# readerstation.net
KiCad netlist of a schematic drawn in EAGLE
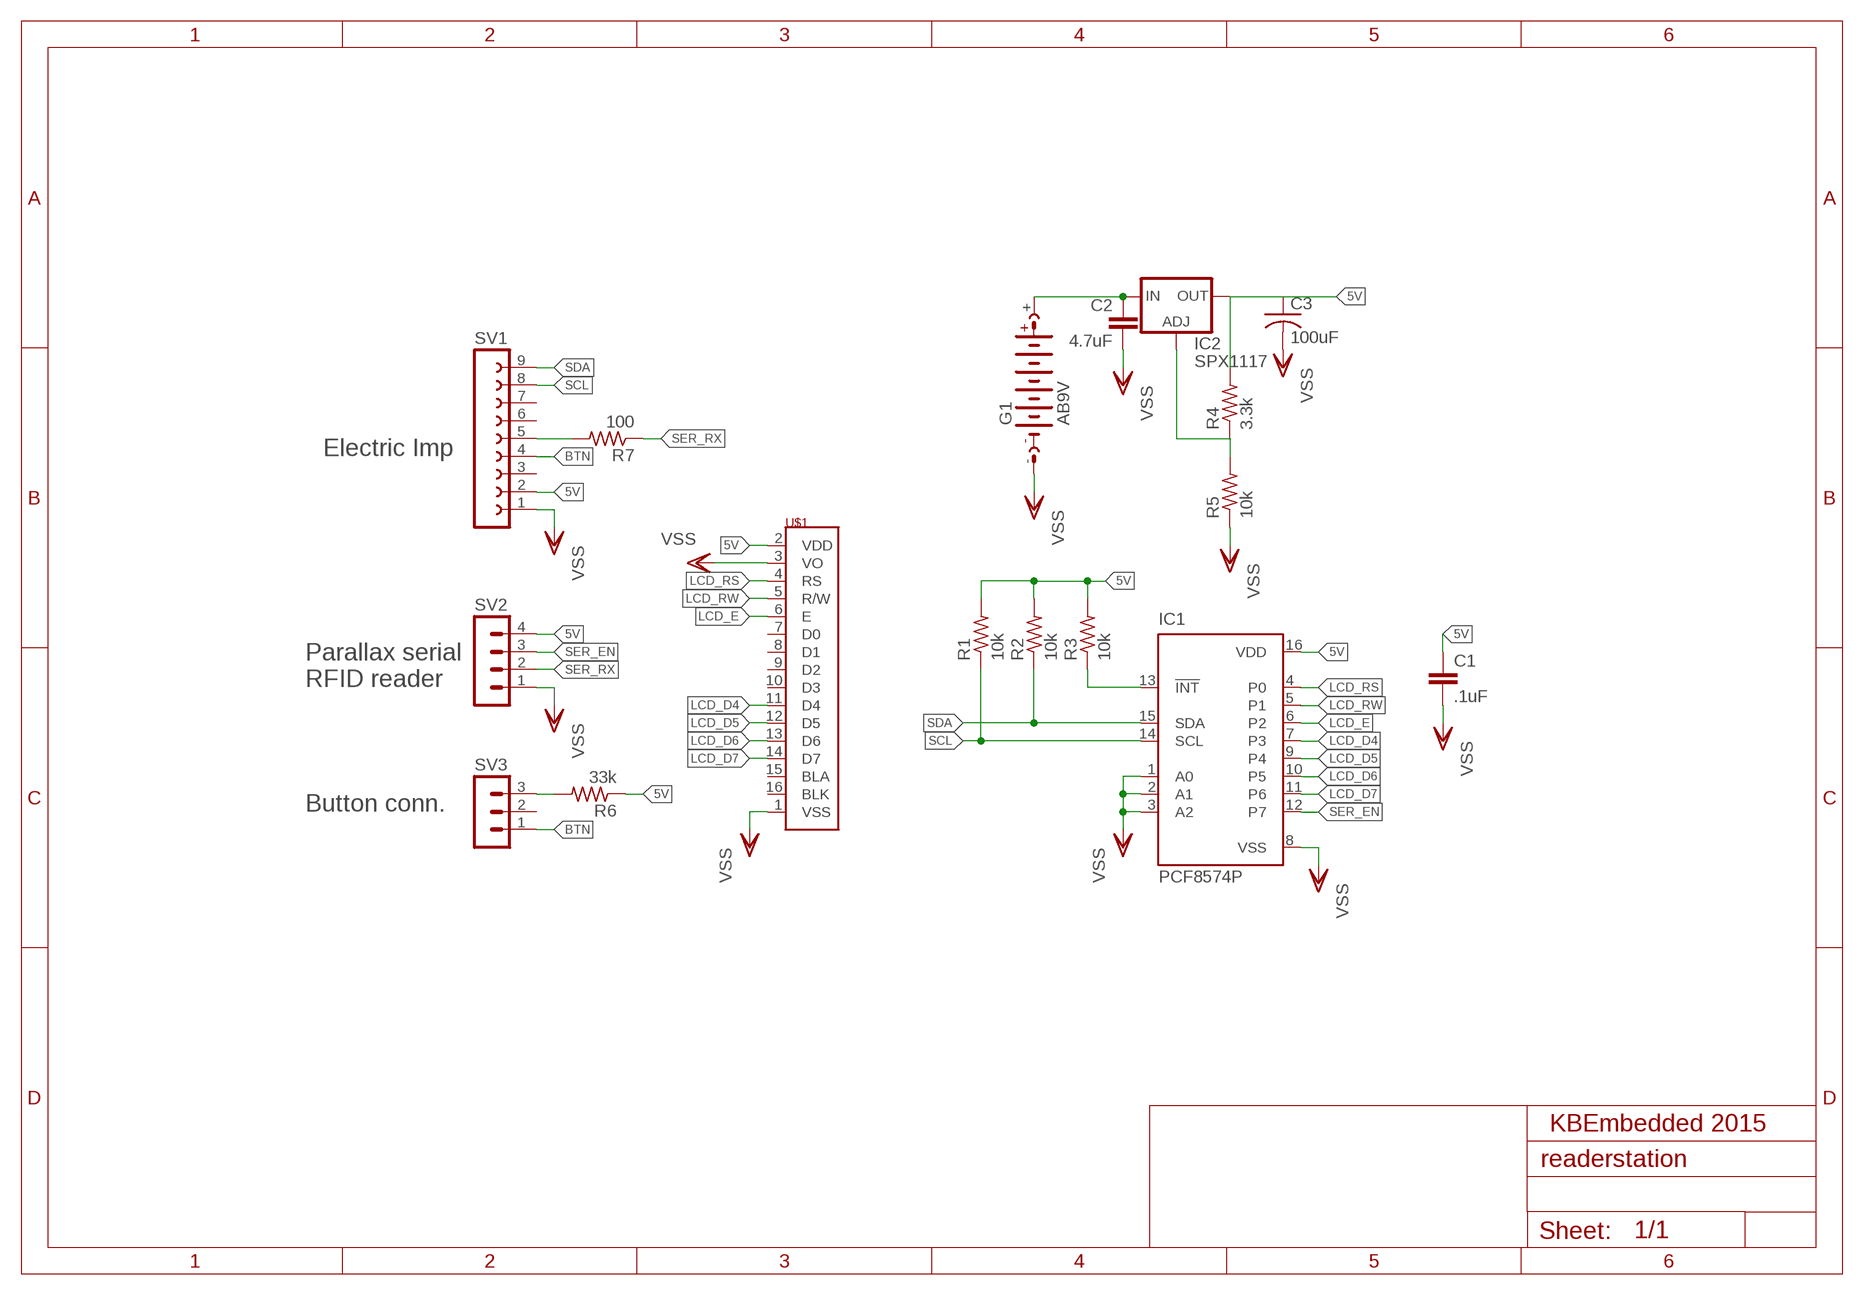
[diagram p0: schematic, sheet 1]

(export (version "E")
  (design (tool "Eeschema 10.0.6"))
  (components
    (comp (ref "C1")
      (value ".1uF")
      (footprint "eagle-import:C025-024X044")
      (libsource (lib "eagle-import") (part "C-EU025-024X044"))
    )
    (comp (ref "C2")
      (value "4.7uF")
      (footprint "eagle-import:C025-024X044")
      (libsource (lib "eagle-import") (part "C-EU025-024X044"))
    )
    (comp (ref "C3")
      (value "100uF")
      (footprint "eagle-import:C025-024X044")
      (libsource (lib "eagle-import") (part "C-US025-024X044"))
    )
    (comp (ref "G1")
      (value "AB9V")
      (footprint "eagle-import:AB9V")
      (libsource (lib "eagle-import") (part "AB9V"))
    )
    (comp (ref "IC1")
      (value "PCF8574P")
      (footprint "eagle-import:DIL16")
      (fields (field (name "MPN") "PCF8574PN"))
      (libsource (lib "eagle-import") (part "PCF8574P"))
    )
    (comp (ref "IC2")
      (value "SPX1117")
      (footprint "eagle-import:SOT223")
      (libsource (lib "eagle-import") (part "LD117A?S12TR"))
    )
    (comp (ref "R1")
      (value "10k")
      (footprint "eagle-import:0204_5")
      (libsource (lib "eagle-import") (part "R-US_0204/5"))
    )
    (comp (ref "R2")
      (value "10k")
      (footprint "eagle-import:0204_5")
      (libsource (lib "eagle-import") (part "R-US_0204/5"))
    )
    (comp (ref "R3")
      (value "10k")
      (footprint "eagle-import:0204_5")
      (libsource (lib "eagle-import") (part "R-US_0204/5"))
    )
    (comp (ref "R4")
      (value "3.3k")
      (footprint "eagle-import:0204_5")
      (libsource (lib "eagle-import") (part "R-US_0204/5"))
    )
    (comp (ref "R5")
      (value "10k")
      (footprint "eagle-import:0204_5")
      (libsource (lib "eagle-import") (part "R-US_0204/5"))
    )
    (comp (ref "R6")
      (value "33k")
      (footprint "eagle-import:0204_5")
      (libsource (lib "eagle-import") (part "R-US_0204/5"))
    )
    (comp (ref "R7")
      (value "100")
      (footprint "eagle-import:0204_5")
      (libsource (lib "eagle-import") (part "R-US_0204/5"))
    )
    (comp (ref "SV1")
      (value "FE09-1")
      (footprint "eagle-import:FE09")
      (libsource (lib "eagle-import") (part "FE09-1"))
    )
    (comp (ref "SV2")
      (value "MA04-1")
      (footprint "eagle-import:MA04-1")
      (libsource (lib "eagle-import") (part "MA04-1"))
    )
    (comp (ref "SV3")
      (value "MA03-1")
      (footprint "eagle-import:MA03-1")
      (libsource (lib "eagle-import") (part "MA03-1"))
    )
    (comp (ref "U$1")
      (value "TRULY_2X16_CHARLCD")
      (footprint "eagle-import:TRULY_2X16_CHARLCD")
      (libsource (lib "eagle-import") (part "TRULY_2X16_CHARLCD"))
    )
  )
  (nets
    (net (code "1") (name "5V") (class "Default")
      (node (ref "C1") (pin "1") (pinfunction "1_1") (pintype "passive"))
      (node (ref "C3") (pin "1") (pinfunction "1_1") (pintype "passive"))
      (node (ref "IC1") (pin "16") (pinfunction "VDD_16") (pintype "power_in"))
      (node (ref "IC2") (pin "4") (pinfunction "OUT_4") (pintype "passive"))
      (node (ref "R1") (pin "2") (pinfunction "2_2") (pintype "passive"))
      (node (ref "R2") (pin "2") (pinfunction "2_2") (pintype "passive"))
      (node (ref "R3") (pin "2") (pinfunction "2_2") (pintype "passive"))
      (node (ref "R4") (pin "2") (pinfunction "2_2") (pintype "passive"))
      (node (ref "R6") (pin "1") (pinfunction "1_1") (pintype "passive"))
      (node (ref "SV1") (pin "2") (pinfunction "2_2") (pintype "passive"))
      (node (ref "SV2") (pin "4") (pinfunction "4_4") (pintype "passive"))
      (node (ref "U$1") (pin "2") (pinfunction "VDD_2") (pintype "bidirectional"))
    )
    (net (code "2") (name "BTN") (class "Default")
      (node (ref "SV1") (pin "4") (pinfunction "4_4") (pintype "passive"))
      (node (ref "SV3") (pin "1") (pinfunction "1_1") (pintype "passive"))
    )
    (net (code "3") (name "LCD_D4") (class "Default")
      (node (ref "IC1") (pin "7") (pinfunction "P3_7") (pintype "bidirectional"))
      (node (ref "U$1") (pin "11") (pinfunction "D4_11") (pintype "bidirectional"))
    )
    (net (code "4") (name "LCD_D5") (class "Default")
      (node (ref "IC1") (pin "9") (pinfunction "P4_9") (pintype "bidirectional"))
      (node (ref "U$1") (pin "12") (pinfunction "D5_12") (pintype "bidirectional"))
    )
    (net (code "5") (name "LCD_D6") (class "Default")
      (node (ref "IC1") (pin "10") (pinfunction "P5_10") (pintype "bidirectional"))
      (node (ref "U$1") (pin "13") (pinfunction "D6_13") (pintype "bidirectional"))
    )
    (net (code "6") (name "LCD_D7") (class "Default")
      (node (ref "IC1") (pin "11") (pinfunction "P6_11") (pintype "bidirectional"))
      (node (ref "U$1") (pin "14") (pinfunction "D7_14") (pintype "bidirectional"))
    )
    (net (code "7") (name "LCD_E") (class "Default")
      (node (ref "IC1") (pin "6") (pinfunction "P2_6") (pintype "bidirectional"))
      (node (ref "U$1") (pin "6") (pinfunction "E_6") (pintype "bidirectional"))
    )
    (net (code "8") (name "LCD_RS") (class "Default")
      (node (ref "IC1") (pin "4") (pinfunction "P0_4") (pintype "bidirectional"))
      (node (ref "U$1") (pin "4") (pinfunction "RS_4") (pintype "bidirectional"))
    )
    (net (code "9") (name "LCD_RW") (class "Default")
      (node (ref "IC1") (pin "5") (pinfunction "P1_5") (pintype "bidirectional"))
      (node (ref "U$1") (pin "5") (pinfunction "R/W_5") (pintype "bidirectional"))
    )
    (net (code "10") (name "Net-(IC1-~{INT})") (class "Default")
      (node (ref "IC1") (pin "13") (pinfunction "~{INT}_13") (pintype "output"))
      (node (ref "R3") (pin "1") (pinfunction "1_1") (pintype "passive"))
    )
    (net (code "11") (name "Net-(IC2-ADJ)") (class "Default")
      (node (ref "IC2") (pin "1") (pinfunction "ADJ_1") (pintype "input"))
      (node (ref "R4") (pin "1") (pinfunction "1_1") (pintype "passive"))
      (node (ref "R5") (pin "2") (pinfunction "2_2") (pintype "passive"))
    )
    (net (code "12") (name "Net-(IC2-IN)") (class "Default")
      (node (ref "C2") (pin "1") (pinfunction "1_1") (pintype "passive"))
      (node (ref "G1") (pin "+") (pinfunction "+_+") (pintype "passive"))
      (node (ref "IC2") (pin "3") (pinfunction "IN_3") (pintype "input"))
    )
    (net (code "13") (name "Net-(R6-Pad2)") (class "Default")
      (node (ref "R6") (pin "2") (pinfunction "2_2") (pintype "passive"))
      (node (ref "SV3") (pin "3") (pinfunction "3_3") (pintype "passive"))
    )
    (net (code "14") (name "Net-(R7-Pad2)") (class "Default")
      (node (ref "R7") (pin "2") (pinfunction "2_2") (pintype "passive"))
      (node (ref "SV1") (pin "5") (pinfunction "5_5") (pintype "passive"))
    )
    (net (code "15") (name "SCL") (class "Default")
      (node (ref "IC1") (pin "14") (pinfunction "SCL_14") (pintype "input"))
      (node (ref "R1") (pin "1") (pinfunction "1_1") (pintype "passive"))
      (node (ref "SV1") (pin "8") (pinfunction "8_8") (pintype "passive"))
    )
    (net (code "16") (name "SDA") (class "Default")
      (node (ref "IC1") (pin "15") (pinfunction "SDA_15") (pintype "bidirectional"))
      (node (ref "R2") (pin "1") (pinfunction "1_1") (pintype "passive"))
      (node (ref "SV1") (pin "9") (pinfunction "9_9") (pintype "passive"))
    )
    (net (code "17") (name "SER_EN") (class "Default")
      (node (ref "IC1") (pin "12") (pinfunction "P7_12") (pintype "bidirectional"))
      (node (ref "SV2") (pin "3") (pinfunction "3_3") (pintype "passive"))
    )
    (net (code "18") (name "SER_RX") (class "Default")
      (node (ref "R7") (pin "1") (pinfunction "1_1") (pintype "passive"))
      (node (ref "SV2") (pin "2") (pinfunction "2_2") (pintype "passive"))
    )
    (net (code "19") (name "VSS") (class "Default")
      (node (ref "C1") (pin "2") (pinfunction "2_2") (pintype "passive"))
      (node (ref "C2") (pin "2") (pinfunction "2_2") (pintype "passive"))
      (node (ref "C3") (pin "2") (pinfunction "2_2") (pintype "passive"))
      (node (ref "G1") (pin "-") (pinfunction "-_-") (pintype "passive"))
      (node (ref "IC1") (pin "1") (pinfunction "A0_1") (pintype "input"))
      (node (ref "IC1") (pin "2") (pinfunction "A1_2") (pintype "input"))
      (node (ref "IC1") (pin "3") (pinfunction "A2_3") (pintype "input"))
      (node (ref "IC1") (pin "8") (pinfunction "VSS_8") (pintype "power_in"))
      (node (ref "R5") (pin "1") (pinfunction "1_1") (pintype "passive"))
      (node (ref "SV1") (pin "1") (pinfunction "1_1") (pintype "passive"))
      (node (ref "U$1") (pin "1") (pinfunction "VSS_1") (pintype "bidirectional"))
      (node (ref "U$1") (pin "3") (pinfunction "VO_3") (pintype "bidirectional"))
    )
    (net (code "20") (name "unconnected-(SV1-Pad3)") (class "Default")
      (node (ref "SV1") (pin "3") (pinfunction "3_3") (pintype "passive"))
    )
    (net (code "21") (name "unconnected-(SV1-Pad6)") (class "Default")
      (node (ref "SV1") (pin "6") (pinfunction "6_6") (pintype "passive"))
    )
    (net (code "22") (name "unconnected-(SV1-Pad7)") (class "Default")
      (node (ref "SV1") (pin "7") (pinfunction "7_7") (pintype "passive"))
    )
    (net (code "23") (name "unconnected-(SV2-Pad1)") (class "Default")
      (node (ref "SV2") (pin "1") (pinfunction "1_1") (pintype "passive"))
    )
    (net (code "24") (name "unconnected-(SV3-Pad2)") (class "Default")
      (node (ref "SV3") (pin "2") (pinfunction "2_2") (pintype "passive"))
    )
    (net (code "25") (name "unconnected-(U$1-BLA-Pad15)") (class "Default")
      (node (ref "U$1") (pin "15") (pinfunction "BLA_15") (pintype "bidirectional"))
    )
    (net (code "26") (name "unconnected-(U$1-BLK-Pad16)") (class "Default")
      (node (ref "U$1") (pin "16") (pinfunction "BLK_16") (pintype "bidirectional"))
    )
    (net (code "27") (name "unconnected-(U$1-D0-Pad7)") (class "Default")
      (node (ref "U$1") (pin "7") (pinfunction "D0_7") (pintype "bidirectional"))
    )
    (net (code "28") (name "unconnected-(U$1-D1-Pad8)") (class "Default")
      (node (ref "U$1") (pin "8") (pinfunction "D1_8") (pintype "bidirectional"))
    )
    (net (code "29") (name "unconnected-(U$1-D2-Pad9)") (class "Default")
      (node (ref "U$1") (pin "9") (pinfunction "D2_9") (pintype "bidirectional"))
    )
    (net (code "30") (name "unconnected-(U$1-D3-Pad10)") (class "Default")
      (node (ref "U$1") (pin "10") (pinfunction "D3_10") (pintype "bidirectional"))
    )
  )
)
